# 808sn.net
KiCad netlist of a schematic drawn in EAGLE
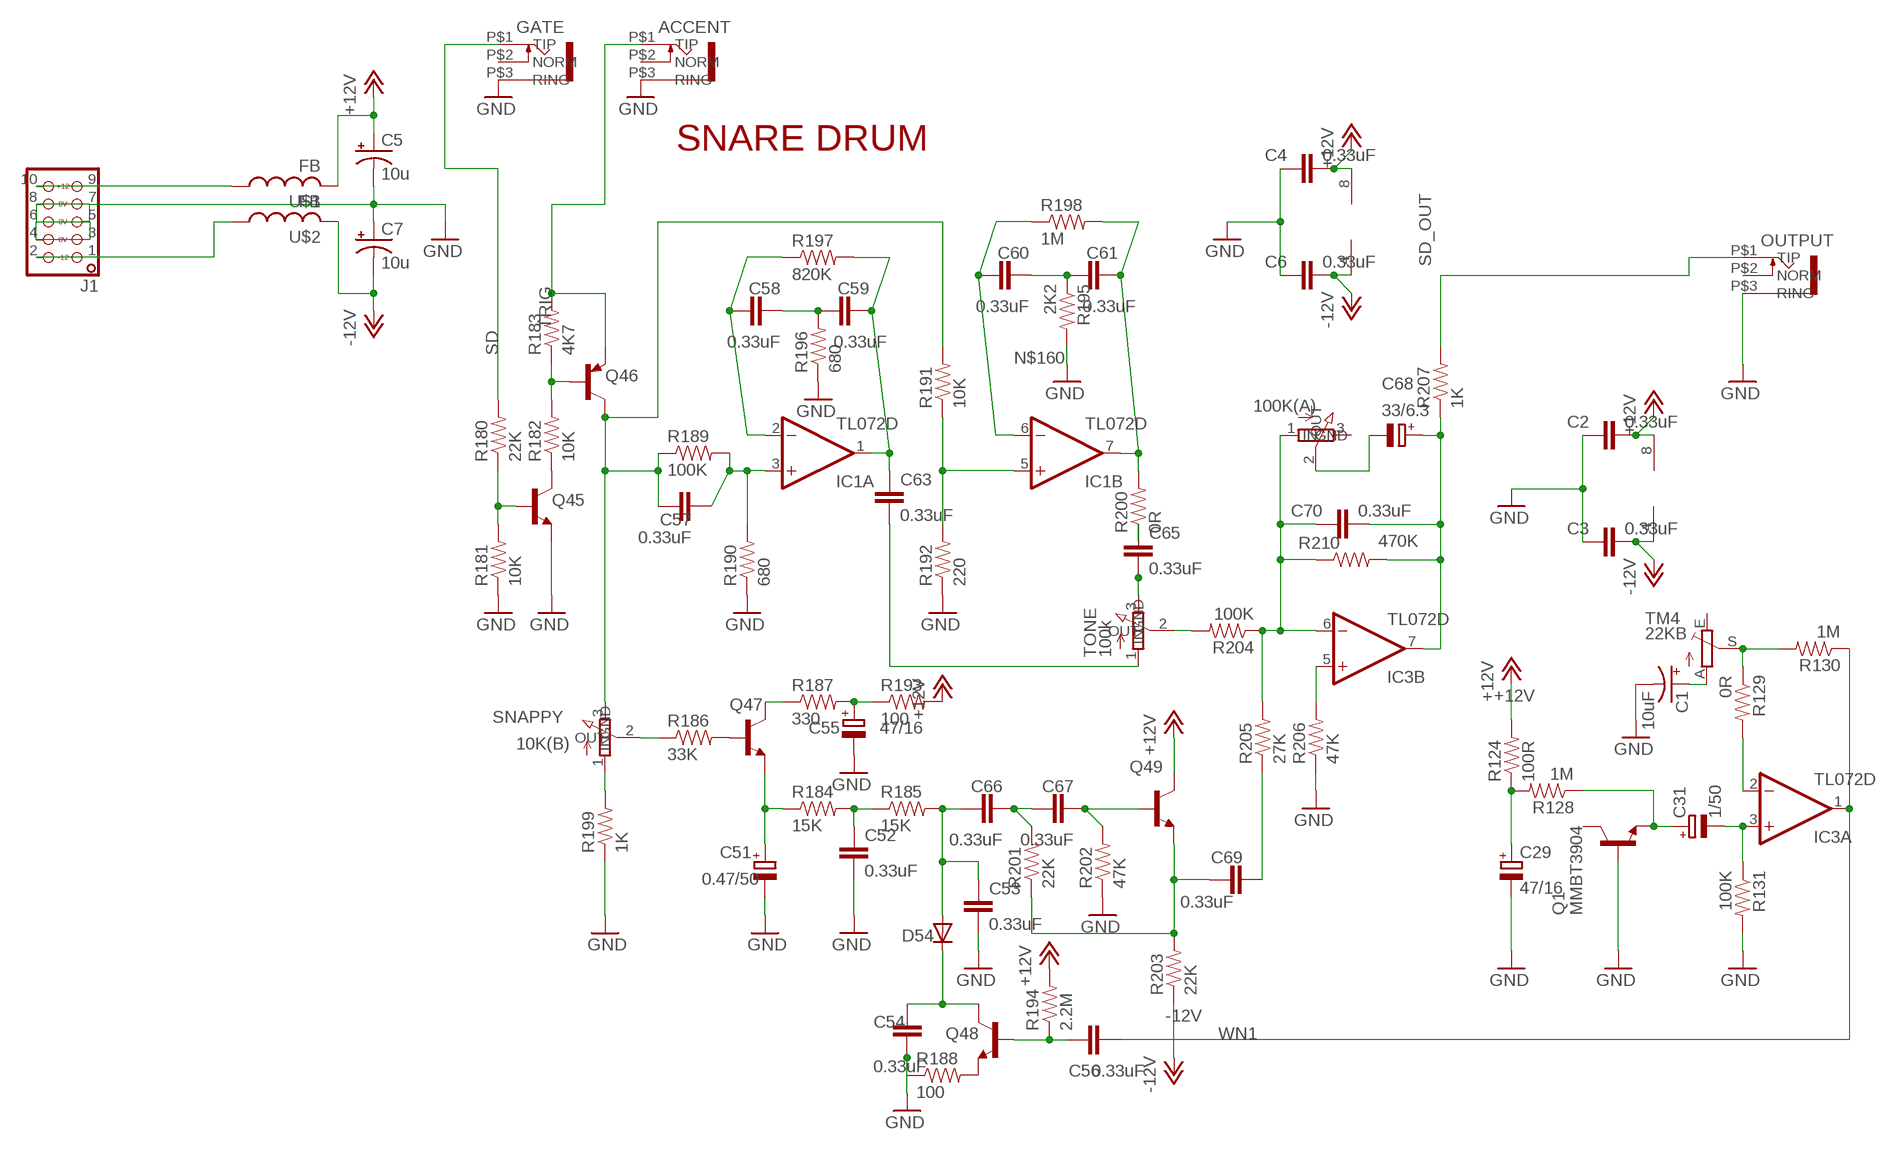
[diagram p0: schematic, sheet 1]

(export (version "E")
  (design (tool "Eeschema 10.0.6"))
  (components
    (comp (ref "ACCENT")
      (value "VERTICALJACKS")
      (footprint "eagle-import:KOBICONN_PJM301DM_JACK")
      (libsource (lib "eagle-import") (part "VERTICALJACKS"))
    )
    (comp (ref "C1")
      (value "10uF")
      (footprint "eagle-import:B45181A")
      (libsource (lib "eagle-import") (part "CPOL-USB45181A"))
    )
    (comp (ref "C2")
      (value "0.33uF")
      (footprint "eagle-import:0805-CAP")
      (libsource (lib "eagle-import") (part "CAPACITOR_0805_HAND"))
    )
    (comp (ref "C3")
      (value "0.33uF")
      (footprint "eagle-import:0805-CAP")
      (libsource (lib "eagle-import") (part "CAPACITOR_0805_HAND"))
    )
    (comp (ref "C4")
      (value "0.33uF")
      (footprint "eagle-import:0805-CAP")
      (libsource (lib "eagle-import") (part "CAPACITOR_0805_HAND"))
    )
    (comp (ref "C5")
      (value "10u")
      (footprint "eagle-import:B45181A")
      (libsource (lib "eagle-import") (part "CPOL-USB45181A"))
    )
    (comp (ref "C6")
      (value "0.33uF")
      (footprint "eagle-import:0805-CAP")
      (libsource (lib "eagle-import") (part "CAPACITOR_0805_HAND"))
    )
    (comp (ref "C7")
      (value "10u")
      (footprint "eagle-import:B45181A")
      (libsource (lib "eagle-import") (part "CPOL-USB45181A"))
    )
    (comp (ref "C29")
      (value "47/16")
      (footprint "eagle-import:E2,5-5")
      (libsource (lib "eagle-import") (part "CPOL-EUE2.5-5"))
    )
    (comp (ref "C31")
      (value "1/50")
      (footprint "eagle-import:E3,5-8")
      (libsource (lib "eagle-import") (part "CPOL-EUE3.5-8"))
    )
    (comp (ref "C51")
      (value "0.47/50")
      (footprint "eagle-import:E3,5-8")
      (libsource (lib "eagle-import") (part "CPOL-EUE3.5-8"))
    )
    (comp (ref "C52")
      (value "0.33uF")
      (footprint "eagle-import:0805-CAP")
      (libsource (lib "eagle-import") (part "CAPACITOR_0805_HAND"))
    )
    (comp (ref "C53")
      (value "0.33uF")
      (footprint "eagle-import:0805-CAP")
      (libsource (lib "eagle-import") (part "CAPACITOR_0805_HAND"))
    )
    (comp (ref "C54")
      (value "0.33uF")
      (footprint "eagle-import:0805-CAP")
      (libsource (lib "eagle-import") (part "CAPACITOR_0805_HAND"))
    )
    (comp (ref "C55")
      (value "47/16")
      (footprint "eagle-import:E2-5")
      (libsource (lib "eagle-import") (part "CPOL-EUE2-5"))
    )
    (comp (ref "C56")
      (value "0.33uF")
      (footprint "eagle-import:0805-CAP")
      (libsource (lib "eagle-import") (part "CAPACITOR_0805_HAND"))
    )
    (comp (ref "C57")
      (value "0.33uF")
      (footprint "eagle-import:0805-CAP")
      (libsource (lib "eagle-import") (part "CAPACITOR_0805_HAND"))
    )
    (comp (ref "C58")
      (value "0.33uF")
      (footprint "eagle-import:0805-CAP")
      (libsource (lib "eagle-import") (part "CAPACITOR_0805_HAND"))
    )
    (comp (ref "C59")
      (value "0.33uF")
      (footprint "eagle-import:0805-CAP")
      (libsource (lib "eagle-import") (part "CAPACITOR_0805_HAND"))
    )
    (comp (ref "C60")
      (value "0.33uF")
      (footprint "eagle-import:0805-CAP")
      (libsource (lib "eagle-import") (part "CAPACITOR_0805_HAND"))
    )
    (comp (ref "C61")
      (value "0.33uF")
      (footprint "eagle-import:0805-CAP")
      (libsource (lib "eagle-import") (part "CAPACITOR_0805_HAND"))
    )
    (comp (ref "C63")
      (value "0.33uF")
      (footprint "eagle-import:0805-CAP")
      (libsource (lib "eagle-import") (part "CAPACITOR_0805_HAND"))
    )
    (comp (ref "C65")
      (value "0.33uF")
      (footprint "eagle-import:0805-CAP")
      (libsource (lib "eagle-import") (part "CAPACITOR_0805_HAND"))
    )
    (comp (ref "C66")
      (value "0.33uF")
      (footprint "eagle-import:0805-CAP")
      (libsource (lib "eagle-import") (part "CAPACITOR_0805_HAND"))
    )
    (comp (ref "C67")
      (value "0.33uF")
      (footprint "eagle-import:0805-CAP")
      (libsource (lib "eagle-import") (part "CAPACITOR_0805_HAND"))
    )
    (comp (ref "C68")
      (value "33/6.3")
      (footprint "eagle-import:E2-5")
      (libsource (lib "eagle-import") (part "CPOL-EUE2-5"))
    )
    (comp (ref "C69")
      (value "0.33uF")
      (footprint "eagle-import:0805-CAP")
      (libsource (lib "eagle-import") (part "CAPACITOR_0805_HAND"))
    )
    (comp (ref "C70")
      (value "0.33uF")
      (footprint "eagle-import:0805-CAP")
      (libsource (lib "eagle-import") (part "CAPACITOR_0805_HAND"))
    )
    (comp (ref "D54")
      (value "1N4148SOD-323")
      (footprint "eagle-import:SOD323W_INFINEON")
      (libsource (lib "eagle-import") (part "1N4148SOD-323"))
    )
    (comp (ref "GATE")
      (value "VERTICALJACKS")
      (footprint "eagle-import:KOBICONN_PJM301DM_JACK")
      (libsource (lib "eagle-import") (part "VERTICALJACKS"))
    )
    (comp (ref "IC1")
      (value "TL072D")
      (footprint "eagle-import:SO08")
      (libsource (lib "eagle-import") (part "TL072D"))
    )
    (comp (ref "IC3")
      (value "TL072D")
      (footprint "eagle-import:SO08")
      (libsource (lib "eagle-import") (part "TL072D"))
    )
    (comp (ref "J1")
      (value "EUROPWR_2X05-OPEN")
      (footprint "eagle-import:2X05_EUROPWR_OPEN")
      (libsource (lib "eagle-import") (part "EUROPWR_2X05-OPEN"))
    )
    (comp (ref "LEVEL")
      (value "100K(A)")
      (footprint "eagle-import:ALPHA_9MM_VERTICAL")
      (libsource (lib "eagle-import") (part "PCB_POTS"))
    )
    (comp (ref "OUTPUT")
      (value "VERTICALJACKS")
      (footprint "eagle-import:KOBICONN_PJM301DM_JACK")
      (libsource (lib "eagle-import") (part "VERTICALJACKS"))
    )
    (comp (ref "Q1")
      (value "MMBT3904")
      (footprint "eagle-import:SOT23-BEC")
      (libsource (lib "eagle-import") (part "-NPN-SOT23-BECMMBT3904LT1"))
    )
    (comp (ref "Q45")
      (value "MMBT3904")
      (footprint "eagle-import:SOT23-BEC")
      (libsource (lib "eagle-import") (part "-NPN-SOT23-BECMMBT3904LT1"))
    )
    (comp (ref "Q46")
      (value "MMBT3906")
      (footprint "eagle-import:SOT23-BEC")
      (libsource (lib "eagle-import") (part "-PNP-SOT23-BECMMBT3906LT1"))
    )
    (comp (ref "Q47")
      (value "MMBT3904")
      (footprint "eagle-import:SOT23-BEC")
      (libsource (lib "eagle-import") (part "-NPN-SOT23-BECMMBT3904LT1"))
    )
    (comp (ref "Q48")
      (value "MMBT3904")
      (footprint "eagle-import:SOT23-BEC")
      (libsource (lib "eagle-import") (part "-NPN-SOT23-BECMMBT3904LT1"))
    )
    (comp (ref "Q49")
      (value "MMBT3904")
      (footprint "eagle-import:SOT23-BEC")
      (libsource (lib "eagle-import") (part "-NPN-SOT23-BECMMBT3904LT1"))
    )
    (comp (ref "R124")
      (value "100R")
      (footprint "eagle-import:0805_RESISTOR")
      (libsource (lib "eagle-import") (part "RESISTOR_0805_HAND"))
    )
    (comp (ref "R128")
      (value "1M")
      (footprint "eagle-import:0805_RESISTOR")
      (libsource (lib "eagle-import") (part "RESISTOR_0805_HAND"))
    )
    (comp (ref "R129")
      (value "0R")
      (footprint "eagle-import:0805_RESISTOR")
      (libsource (lib "eagle-import") (part "RESISTOR_0805_HAND"))
    )
    (comp (ref "R130")
      (value "1M")
      (footprint "eagle-import:0805_RESISTOR")
      (libsource (lib "eagle-import") (part "RESISTOR_0805_HAND"))
    )
    (comp (ref "R131")
      (value "100K")
      (footprint "eagle-import:0805_RESISTOR")
      (libsource (lib "eagle-import") (part "RESISTOR_0805_HAND"))
    )
    (comp (ref "R180")
      (value "22K")
      (footprint "eagle-import:0805_RESISTOR")
      (libsource (lib "eagle-import") (part "RESISTOR_0805_HAND"))
    )
    (comp (ref "R181")
      (value "10K")
      (footprint "eagle-import:0805_RESISTOR")
      (libsource (lib "eagle-import") (part "RESISTOR_0805_HAND"))
    )
    (comp (ref "R182")
      (value "10K")
      (footprint "eagle-import:0805_RESISTOR")
      (libsource (lib "eagle-import") (part "RESISTOR_0805_HAND"))
    )
    (comp (ref "R183")
      (value "4K7")
      (footprint "eagle-import:0805_RESISTOR")
      (libsource (lib "eagle-import") (part "RESISTOR_0805_HAND"))
    )
    (comp (ref "R184")
      (value "15K")
      (footprint "eagle-import:0805_RESISTOR")
      (libsource (lib "eagle-import") (part "RESISTOR_0805_HAND"))
    )
    (comp (ref "R185")
      (value "15K")
      (footprint "eagle-import:0805_RESISTOR")
      (libsource (lib "eagle-import") (part "RESISTOR_0805_HAND"))
    )
    (comp (ref "R186")
      (value "33K")
      (footprint "eagle-import:0805_RESISTOR")
      (libsource (lib "eagle-import") (part "RESISTOR_0805_HAND"))
    )
    (comp (ref "R187")
      (value "330")
      (footprint "eagle-import:0805_RESISTOR")
      (libsource (lib "eagle-import") (part "RESISTOR_0805_HAND"))
    )
    (comp (ref "R188")
      (value "100")
      (footprint "eagle-import:0805_RESISTOR")
      (libsource (lib "eagle-import") (part "RESISTOR_0805_HAND"))
    )
    (comp (ref "R189")
      (value "100K")
      (footprint "eagle-import:0805_RESISTOR")
      (libsource (lib "eagle-import") (part "RESISTOR_0805_HAND"))
    )
    (comp (ref "R190")
      (value "680")
      (footprint "eagle-import:0805_RESISTOR")
      (libsource (lib "eagle-import") (part "RESISTOR_0805_HAND"))
    )
    (comp (ref "R191")
      (value "10K")
      (footprint "eagle-import:0805_RESISTOR")
      (libsource (lib "eagle-import") (part "RESISTOR_0805_HAND"))
    )
    (comp (ref "R192")
      (value "220")
      (footprint "eagle-import:0805_RESISTOR")
      (libsource (lib "eagle-import") (part "RESISTOR_0805_HAND"))
    )
    (comp (ref "R193")
      (value "100")
      (footprint "eagle-import:0805_RESISTOR")
      (libsource (lib "eagle-import") (part "RESISTOR_0805_HAND"))
    )
    (comp (ref "R194")
      (value "2.2M")
      (footprint "eagle-import:0805_RESISTOR")
      (libsource (lib "eagle-import") (part "RESISTOR_0805_HAND"))
    )
    (comp (ref "R195")
      (value "2K2")
      (footprint "eagle-import:0805_RESISTOR")
      (libsource (lib "eagle-import") (part "RESISTOR_0805_HAND"))
    )
    (comp (ref "R196")
      (value "680")
      (footprint "eagle-import:0805_RESISTOR")
      (libsource (lib "eagle-import") (part "RESISTOR_0805_HAND"))
    )
    (comp (ref "R197")
      (value "820K")
      (footprint "eagle-import:0805_RESISTOR")
      (libsource (lib "eagle-import") (part "RESISTOR_0805_HAND"))
    )
    (comp (ref "R198")
      (value "1M")
      (footprint "eagle-import:0805_RESISTOR")
      (libsource (lib "eagle-import") (part "RESISTOR_0805_HAND"))
    )
    (comp (ref "R199")
      (value "1K")
      (footprint "eagle-import:0805_RESISTOR")
      (libsource (lib "eagle-import") (part "RESISTOR_0805_HAND"))
    )
    (comp (ref "R200")
      (value "0R")
      (footprint "eagle-import:0805_RESISTOR")
      (libsource (lib "eagle-import") (part "RESISTOR_0805_HAND"))
    )
    (comp (ref "R201")
      (value "22K")
      (footprint "eagle-import:0805_RESISTOR")
      (libsource (lib "eagle-import") (part "RESISTOR_0805_HAND"))
    )
    (comp (ref "R202")
      (value "47K")
      (footprint "eagle-import:0805_RESISTOR")
      (libsource (lib "eagle-import") (part "RESISTOR_0805_HAND"))
    )
    (comp (ref "R203")
      (value "22K")
      (footprint "eagle-import:0805_RESISTOR")
      (libsource (lib "eagle-import") (part "RESISTOR_0805_HAND"))
    )
    (comp (ref "R204")
      (value "100K")
      (footprint "eagle-import:0805_RESISTOR")
      (libsource (lib "eagle-import") (part "RESISTOR_0805_HAND"))
    )
    (comp (ref "R205")
      (value "27K")
      (footprint "eagle-import:0805_RESISTOR")
      (libsource (lib "eagle-import") (part "RESISTOR_0805_HAND"))
    )
    (comp (ref "R206")
      (value "47K")
      (footprint "eagle-import:0805_RESISTOR")
      (libsource (lib "eagle-import") (part "RESISTOR_0805_HAND"))
    )
    (comp (ref "R207")
      (value "1K")
      (footprint "eagle-import:0805_RESISTOR")
      (libsource (lib "eagle-import") (part "RESISTOR_0805_HAND"))
    )
    (comp (ref "R210")
      (value "470K")
      (footprint "eagle-import:0805_RESISTOR")
      (libsource (lib "eagle-import") (part "RESISTOR_0805_HAND"))
    )
    (comp (ref "SNAPPY")
      (value "10K(B)")
      (footprint "eagle-import:ALPHA_9MM_VERTICAL")
      (libsource (lib "eagle-import") (part "PCB_POTS"))
    )
    (comp (ref "TM4")
      (value "22KB")
      (footprint "eagle-import:B64Y")
      (libsource (lib "eagle-import") (part "TRIM_EU-B64Y"))
    )
    (comp (ref "TONE")
      (value "100k")
      (footprint "eagle-import:ALPHA_9MM_VERTICAL")
      (libsource (lib "eagle-import") (part "PCB_POTS"))
    )
    (comp (ref "U$1") (value "FB") (footprint "eagle-import:FB") (libsource (lib "eagle-import") (part "FB")))
    (comp (ref "U$2") (value "FB") (footprint "eagle-import:FB") (libsource (lib "eagle-import") (part "FB")))
  )
  (nets
    (net (code "1") (name "+12V") (class "Default")
      (node (ref "C2") (pin "2") (pinfunction "2_2") (pintype "passive"))
      (node (ref "C4") (pin "2") (pinfunction "2_2") (pintype "passive"))
      (node (ref "C5") (pin "+") (pinfunction "+_+") (pintype "passive"))
      (node (ref "IC1") (pin "8") (pinfunction "V+_8") (pintype "power_in"))
      (node (ref "IC3") (pin "8") (pinfunction "V+_8") (pintype "power_in"))
      (node (ref "Q49") (pin "C") (pinfunction "C_C") (pintype "passive"))
      (node (ref "R124") (pin "2") (pinfunction "2_2") (pintype "passive"))
      (node (ref "R193") (pin "2") (pinfunction "2_2") (pintype "passive"))
      (node (ref "R194") (pin "2") (pinfunction "2_2") (pintype "passive"))
      (node (ref "U$1") (pin "P$2") (pinfunction "2_P$2") (pintype "passive"))
    )
    (net (code "2") (name "-12V") (class "Default")
      (node (ref "C3") (pin "2") (pinfunction "2_2") (pintype "passive"))
      (node (ref "C6") (pin "2") (pinfunction "2_2") (pintype "passive"))
      (node (ref "C7") (pin "-") (pinfunction "-_-") (pintype "passive"))
      (node (ref "IC1") (pin "4") (pinfunction "V-_4") (pintype "power_in"))
      (node (ref "IC3") (pin "4") (pinfunction "V-_4") (pintype "power_in"))
      (node (ref "R203") (pin "1") (pinfunction "1_1") (pintype "passive"))
      (node (ref "U$2") (pin "P$2") (pinfunction "2_P$2") (pintype "passive"))
    )
    (net (code "3") (name "/N$160") (class "Default")
      (node (ref "C60") (pin "1") (pinfunction "1_1") (pintype "passive"))
      (node (ref "IC1") (pin "6") (pinfunction "-IN_6") (pintype "input"))
      (node (ref "R198") (pin "1") (pinfunction "1_1") (pintype "passive"))
    )
    (net (code "4") (name "/SD") (class "Default")
      (node (ref "GATE") (pin "P$1") (pinfunction "TIP_P$1") (pintype "passive"))
      (node (ref "R180") (pin "2") (pinfunction "2_2") (pintype "passive"))
    )
    (net (code "5") (name "/SD_OUT") (class "Default")
      (node (ref "OUTPUT") (pin "P$1") (pinfunction "TIP_P$1") (pintype "passive"))
      (node (ref "R207") (pin "2") (pinfunction "2_2") (pintype "passive"))
    )
    (net (code "6") (name "/TRIG") (class "Default")
      (node (ref "ACCENT") (pin "P$1") (pinfunction "TIP_P$1") (pintype "passive"))
      (node (ref "Q46") (pin "E") (pinfunction "E_E") (pintype "passive"))
      (node (ref "R183") (pin "2") (pinfunction "2_2") (pintype "passive"))
    )
    (net (code "7") (name "/WN1") (class "Default")
      (node (ref "C56") (pin "2") (pinfunction "2_2") (pintype "passive"))
      (node (ref "IC3") (pin "1") (pinfunction "OUT_1") (pintype "output"))
      (node (ref "R130") (pin "1") (pinfunction "1_1") (pintype "passive"))
    )
    (net (code "8") (name "GND") (class "Default")
      (node (ref "ACCENT") (pin "P$3") (pinfunction "RING_P$3") (pintype "passive"))
      (node (ref "C1") (pin "-") (pinfunction "-_-") (pintype "passive"))
      (node (ref "C2") (pin "1") (pinfunction "1_1") (pintype "passive"))
      (node (ref "C29") (pin "-") (pinfunction "-_-") (pintype "passive"))
      (node (ref "C3") (pin "1") (pinfunction "1_1") (pintype "passive"))
      (node (ref "C4") (pin "1") (pinfunction "1_1") (pintype "passive"))
      (node (ref "C5") (pin "-") (pinfunction "-_-") (pintype "passive"))
      (node (ref "C51") (pin "-") (pinfunction "-_-") (pintype "passive"))
      (node (ref "C52") (pin "2") (pinfunction "2_2") (pintype "passive"))
      (node (ref "C53") (pin "2") (pinfunction "2_2") (pintype "passive"))
      (node (ref "C54") (pin "2") (pinfunction "2_2") (pintype "passive"))
      (node (ref "C55") (pin "-") (pinfunction "-_-") (pintype "passive"))
      (node (ref "C6") (pin "1") (pinfunction "1_1") (pintype "passive"))
      (node (ref "C7") (pin "+") (pinfunction "+_+") (pintype "passive"))
      (node (ref "GATE") (pin "P$3") (pinfunction "RING_P$3") (pintype "passive"))
      (node (ref "J1") (pin "3") (pinfunction "3_3") (pintype "passive"))
      (node (ref "J1") (pin "4") (pinfunction "4_4") (pintype "passive"))
      (node (ref "J1") (pin "5") (pinfunction "5_5") (pintype "passive"))
      (node (ref "J1") (pin "6") (pinfunction "6_6") (pintype "passive"))
      (node (ref "J1") (pin "7") (pinfunction "7_7") (pintype "passive"))
      (node (ref "J1") (pin "8") (pinfunction "8_8") (pintype "passive"))
      (node (ref "OUTPUT") (pin "P$3") (pinfunction "RING_P$3") (pintype "passive"))
      (node (ref "Q1") (pin "B") (pinfunction "B_B") (pintype "passive"))
      (node (ref "Q45") (pin "E") (pinfunction "E_E") (pintype "passive"))
      (node (ref "R131") (pin "2") (pinfunction "2_2") (pintype "passive"))
      (node (ref "R181") (pin "1") (pinfunction "1_1") (pintype "passive"))
      (node (ref "R188") (pin "1") (pinfunction "1_1") (pintype "passive"))
      (node (ref "R190") (pin "1") (pinfunction "1_1") (pintype "passive"))
      (node (ref "R192") (pin "1") (pinfunction "1_1") (pintype "passive"))
      (node (ref "R195") (pin "2") (pinfunction "2_2") (pintype "passive"))
      (node (ref "R196") (pin "1") (pinfunction "1_1") (pintype "passive"))
      (node (ref "R199") (pin "1") (pinfunction "1_1") (pintype "passive"))
      (node (ref "R202") (pin "1") (pinfunction "1_1") (pintype "passive"))
      (node (ref "R206") (pin "1") (pinfunction "1_1") (pintype "passive"))
    )
    (net (code "9") (name "Net-(C1-Pad+)") (class "Default")
      (node (ref "C1") (pin "+") (pinfunction "+_+") (pintype "passive"))
      (node (ref "TM4") (pin "A") (pinfunction "A_A") (pintype "passive"))
    )
    (net (code "10") (name "Net-(C29-Pad+)") (class "Default")
      (node (ref "C29") (pin "+") (pinfunction "+_+") (pintype "passive"))
      (node (ref "R124") (pin "1") (pinfunction "1_1") (pintype "passive"))
      (node (ref "R128") (pin "2") (pinfunction "2_2") (pintype "passive"))
    )
    (net (code "11") (name "Net-(C31-Pad+)") (class "Default")
      (node (ref "C31") (pin "+") (pinfunction "+_+") (pintype "passive"))
      (node (ref "Q1") (pin "E") (pinfunction "E_E") (pintype "passive"))
      (node (ref "R128") (pin "1") (pinfunction "1_1") (pintype "passive"))
    )
    (net (code "12") (name "Net-(C51-Pad+)") (class "Default")
      (node (ref "C51") (pin "+") (pinfunction "+_+") (pintype "passive"))
      (node (ref "Q47") (pin "E") (pinfunction "E_E") (pintype "passive"))
      (node (ref "R184") (pin "1") (pinfunction "1_1") (pintype "passive"))
    )
    (net (code "13") (name "Net-(C52-Pad1)") (class "Default")
      (node (ref "C52") (pin "1") (pinfunction "1_1") (pintype "passive"))
      (node (ref "R184") (pin "2") (pinfunction "2_2") (pintype "passive"))
      (node (ref "R185") (pin "1") (pinfunction "1_1") (pintype "passive"))
    )
    (net (code "14") (name "Net-(C53-Pad1)") (class "Default")
      (node (ref "C53") (pin "1") (pinfunction "1_1") (pintype "passive"))
      (node (ref "C66") (pin "1") (pinfunction "1_1") (pintype "passive"))
      (node (ref "D54") (pin "A") (pinfunction "A_A") (pintype "passive"))
      (node (ref "R185") (pin "2") (pinfunction "2_2") (pintype "passive"))
    )
    (net (code "15") (name "Net-(C54-Pad1)") (class "Default")
      (node (ref "C54") (pin "1") (pinfunction "1_1") (pintype "passive"))
      (node (ref "D54") (pin "C") (pinfunction "C_C") (pintype "passive"))
      (node (ref "Q48") (pin "C") (pinfunction "C_C") (pintype "passive"))
    )
    (net (code "16") (name "Net-(C55-Pad+)") (class "Default")
      (node (ref "C55") (pin "+") (pinfunction "+_+") (pintype "passive"))
      (node (ref "R187") (pin "2") (pinfunction "2_2") (pintype "passive"))
      (node (ref "R193") (pin "1") (pinfunction "1_1") (pintype "passive"))
    )
    (net (code "17") (name "Net-(C56-Pad1)") (class "Default")
      (node (ref "C56") (pin "1") (pinfunction "1_1") (pintype "passive"))
      (node (ref "Q48") (pin "B") (pinfunction "B_B") (pintype "passive"))
      (node (ref "R194") (pin "1") (pinfunction "1_1") (pintype "passive"))
    )
    (net (code "18") (name "Net-(C58-Pad2)") (class "Default")
      (node (ref "C58") (pin "2") (pinfunction "2_2") (pintype "passive"))
      (node (ref "C59") (pin "1") (pinfunction "1_1") (pintype "passive"))
      (node (ref "R196") (pin "2") (pinfunction "2_2") (pintype "passive"))
    )
    (net (code "19") (name "Net-(C60-Pad2)") (class "Default")
      (node (ref "C60") (pin "2") (pinfunction "2_2") (pintype "passive"))
      (node (ref "C61") (pin "1") (pinfunction "1_1") (pintype "passive"))
      (node (ref "R195") (pin "1") (pinfunction "1_1") (pintype "passive"))
    )
    (net (code "20") (name "Net-(C65-Pad1)") (class "Default")
      (node (ref "C65") (pin "1") (pinfunction "1_1") (pintype "passive"))
      (node (ref "R200") (pin "1") (pinfunction "1_1") (pintype "passive"))
    )
    (net (code "21") (name "Net-(C66-Pad2)") (class "Default")
      (node (ref "C66") (pin "2") (pinfunction "2_2") (pintype "passive"))
      (node (ref "C67") (pin "1") (pinfunction "1_1") (pintype "passive"))
      (node (ref "R201") (pin "2") (pinfunction "2_2") (pintype "passive"))
    )
    (net (code "22") (name "Net-(C67-Pad2)") (class "Default")
      (node (ref "C67") (pin "2") (pinfunction "2_2") (pintype "passive"))
      (node (ref "Q49") (pin "B") (pinfunction "B_B") (pintype "passive"))
      (node (ref "R202") (pin "2") (pinfunction "2_2") (pintype "passive"))
    )
    (net (code "23") (name "Net-(C69-Pad1)") (class "Default")
      (node (ref "C69") (pin "1") (pinfunction "1_1") (pintype "passive"))
      (node (ref "Q49") (pin "E") (pinfunction "E_E") (pintype "passive"))
      (node (ref "R201") (pin "1") (pinfunction "1_1") (pintype "passive"))
      (node (ref "R203") (pin "2") (pinfunction "2_2") (pintype "passive"))
    )
    (net (code "24") (name "Net-(C69-Pad2)") (class "Default")
      (node (ref "C69") (pin "2") (pinfunction "2_2") (pintype "passive"))
      (node (ref "R205") (pin "1") (pinfunction "1_1") (pintype "passive"))
    )
    (net (code "25") (name "Net-(IC1A-+IN)") (class "Default")
      (node (ref "C57") (pin "2") (pinfunction "2_2") (pintype "passive"))
      (node (ref "IC1") (pin "3") (pinfunction "+IN_3") (pintype "input"))
      (node (ref "R189") (pin "2") (pinfunction "2_2") (pintype "passive"))
      (node (ref "R190") (pin "2") (pinfunction "2_2") (pintype "passive"))
    )
    (net (code "26") (name "Net-(IC1A--IN)") (class "Default")
      (node (ref "C58") (pin "1") (pinfunction "1_1") (pintype "passive"))
      (node (ref "IC1") (pin "2") (pinfunction "-IN_2") (pintype "input"))
      (node (ref "R197") (pin "1") (pinfunction "1_1") (pintype "passive"))
    )
    (net (code "27") (name "Net-(IC1A-OUT)") (class "Default")
      (node (ref "C59") (pin "2") (pinfunction "2_2") (pintype "passive"))
      (node (ref "C63") (pin "1") (pinfunction "1_1") (pintype "passive"))
      (node (ref "IC1") (pin "1") (pinfunction "OUT_1") (pintype "output"))
      (node (ref "R197") (pin "2") (pinfunction "2_2") (pintype "passive"))
    )
    (net (code "28") (name "Net-(IC1B-+IN)") (class "Default")
      (node (ref "IC1") (pin "5") (pinfunction "+IN_5") (pintype "input"))
      (node (ref "R191") (pin "1") (pinfunction "1_1") (pintype "passive"))
      (node (ref "R192") (pin "2") (pinfunction "2_2") (pintype "passive"))
    )
    (net (code "29") (name "Net-(IC1B-OUT)") (class "Default")
      (node (ref "C61") (pin "2") (pinfunction "2_2") (pintype "passive"))
      (node (ref "IC1") (pin "7") (pinfunction "OUT_7") (pintype "output"))
      (node (ref "R198") (pin "2") (pinfunction "2_2") (pintype "passive"))
      (node (ref "R200") (pin "2") (pinfunction "2_2") (pintype "passive"))
    )
    (net (code "30") (name "Net-(IC3A-+IN)") (class "Default")
      (node (ref "C31") (pin "-") (pinfunction "-_-") (pintype "passive"))
      (node (ref "IC3") (pin "3") (pinfunction "+IN_3") (pintype "input"))
      (node (ref "R131") (pin "1") (pinfunction "1_1") (pintype "passive"))
    )
    (net (code "31") (name "Net-(IC3A--IN)") (class "Default")
      (node (ref "IC3") (pin "2") (pinfunction "-IN_2") (pintype "input"))
      (node (ref "R129") (pin "2") (pinfunction "2_2") (pintype "passive"))
    )
    (net (code "32") (name "Net-(IC3B-+IN)") (class "Default")
      (node (ref "IC3") (pin "5") (pinfunction "+IN_5") (pintype "input"))
      (node (ref "R206") (pin "2") (pinfunction "2_2") (pintype "passive"))
    )
    (net (code "33") (name "Net-(IC3B--IN)") (class "Default")
      (node (ref "C70") (pin "1") (pinfunction "1_1") (pintype "passive"))
      (node (ref "IC3") (pin "6") (pinfunction "-IN_6") (pintype "input"))
      (node (ref "LEVEL") (pin "1") (pinfunction "GND_1") (pintype "passive"))
      (node (ref "R204") (pin "1") (pinfunction "1_1") (pintype "passive"))
      (node (ref "R205") (pin "2") (pinfunction "2_2") (pintype "passive"))
      (node (ref "R210") (pin "1") (pinfunction "1_1") (pintype "passive"))
    )
    (net (code "34") (name "Net-(IC3B-OUT)") (class "Default")
      (node (ref "C68") (pin "+") (pinfunction "+_+") (pintype "passive"))
      (node (ref "C70") (pin "2") (pinfunction "2_2") (pintype "passive"))
      (node (ref "IC3") (pin "7") (pinfunction "OUT_7") (pintype "output"))
      (node (ref "R207") (pin "1") (pinfunction "1_1") (pintype "passive"))
      (node (ref "R210") (pin "2") (pinfunction "2_2") (pintype "passive"))
    )
    (net (code "35") (name "Net-(LEVEL-OUT)") (class "Default")
      (node (ref "C68") (pin "-") (pinfunction "-_-") (pintype "passive"))
      (node (ref "LEVEL") (pin "2") (pinfunction "OUT_2") (pintype "passive"))
    )
    (net (code "36") (name "Net-(Q45-PadB)") (class "Default")
      (node (ref "Q45") (pin "B") (pinfunction "B_B") (pintype "passive"))
      (node (ref "R180") (pin "1") (pinfunction "1_1") (pintype "passive"))
      (node (ref "R181") (pin "2") (pinfunction "2_2") (pintype "passive"))
    )
    (net (code "37") (name "Net-(Q45-PadC)") (class "Default")
      (node (ref "Q45") (pin "C") (pinfunction "C_C") (pintype "passive"))
      (node (ref "R182") (pin "1") (pinfunction "1_1") (pintype "passive"))
    )
    (net (code "38") (name "Net-(Q46-PadB)") (class "Default")
      (node (ref "Q46") (pin "B") (pinfunction "B_B") (pintype "passive"))
      (node (ref "R182") (pin "2") (pinfunction "2_2") (pintype "passive"))
      (node (ref "R183") (pin "1") (pinfunction "1_1") (pintype "passive"))
    )
    (net (code "39") (name "Net-(Q47-PadB)") (class "Default")
      (node (ref "Q47") (pin "B") (pinfunction "B_B") (pintype "passive"))
      (node (ref "R186") (pin "2") (pinfunction "2_2") (pintype "passive"))
    )
    (net (code "40") (name "Net-(Q47-PadC)") (class "Default")
      (node (ref "Q47") (pin "C") (pinfunction "C_C") (pintype "passive"))
      (node (ref "R187") (pin "1") (pinfunction "1_1") (pintype "passive"))
    )
    (net (code "41") (name "Net-(Q48-PadE)") (class "Default")
      (node (ref "Q48") (pin "E") (pinfunction "E_E") (pintype "passive"))
      (node (ref "R188") (pin "2") (pinfunction "2_2") (pintype "passive"))
    )
    (net (code "42") (name "Net-(R129-Pad1)") (class "Default")
      (node (ref "R129") (pin "1") (pinfunction "1_1") (pintype "passive"))
      (node (ref "R130") (pin "2") (pinfunction "2_2") (pintype "passive"))
      (node (ref "TM4") (pin "S") (pinfunction "S_S") (pintype "passive"))
    )
    (net (code "43") (name "Net-(SNAPPY-GND)") (class "Default")
      (node (ref "R199") (pin "2") (pinfunction "2_2") (pintype "passive"))
      (node (ref "SNAPPY") (pin "1") (pinfunction "GND_1") (pintype "passive"))
    )
    (net (code "44") (name "Net-(SNAPPY-IN)") (class "Default")
      (node (ref "C57") (pin "1") (pinfunction "1_1") (pintype "passive"))
      (node (ref "Q46") (pin "C") (pinfunction "C_C") (pintype "passive"))
      (node (ref "R189") (pin "1") (pinfunction "1_1") (pintype "passive"))
      (node (ref "R191") (pin "2") (pinfunction "2_2") (pintype "passive"))
      (node (ref "SNAPPY") (pin "3") (pinfunction "IN_3") (pintype "passive"))
    )
    (net (code "45") (name "Net-(SNAPPY-OUT)") (class "Default")
      (node (ref "R186") (pin "1") (pinfunction "1_1") (pintype "passive"))
      (node (ref "SNAPPY") (pin "2") (pinfunction "OUT_2") (pintype "passive"))
    )
    (net (code "46") (name "Net-(TONE-GND)") (class "Default")
      (node (ref "C63") (pin "2") (pinfunction "2_2") (pintype "passive"))
      (node (ref "TONE") (pin "1") (pinfunction "GND_1") (pintype "passive"))
    )
    (net (code "47") (name "Net-(TONE-IN)") (class "Default")
      (node (ref "C65") (pin "2") (pinfunction "2_2") (pintype "passive"))
      (node (ref "TONE") (pin "3") (pinfunction "IN_3") (pintype "passive"))
    )
    (net (code "48") (name "Net-(TONE-OUT)") (class "Default")
      (node (ref "R204") (pin "2") (pinfunction "2_2") (pintype "passive"))
      (node (ref "TONE") (pin "2") (pinfunction "OUT_2") (pintype "passive"))
    )
    (net (code "49") (name "Net-(U$1-1)") (class "Default")
      (node (ref "J1") (pin "10") (pinfunction "10_10") (pintype "passive"))
      (node (ref "J1") (pin "9") (pinfunction "9_9") (pintype "passive"))
      (node (ref "U$1") (pin "P$1") (pinfunction "1_P$1") (pintype "passive"))
    )
    (net (code "50") (name "Net-(U$2-1)") (class "Default")
      (node (ref "J1") (pin "1") (pinfunction "1_1") (pintype "passive"))
      (node (ref "J1") (pin "2") (pinfunction "2_2") (pintype "passive"))
      (node (ref "U$2") (pin "P$1") (pinfunction "1_P$1") (pintype "passive"))
    )
    (net (code "51") (name "unconnected-(ACCENT-NORM-PadP$2)") (class "Default")
      (node (ref "ACCENT") (pin "P$2") (pinfunction "NORM_P$2") (pintype "passive"))
    )
    (net (code "52") (name "unconnected-(GATE-NORM-PadP$2)") (class "Default")
      (node (ref "GATE") (pin "P$2") (pinfunction "NORM_P$2") (pintype "passive"))
    )
    (net (code "53") (name "unconnected-(LEVEL-IN-Pad3)") (class "Default")
      (node (ref "LEVEL") (pin "3") (pinfunction "IN_3") (pintype "passive"))
    )
    (net (code "54") (name "unconnected-(OUTPUT-NORM-PadP$2)") (class "Default")
      (node (ref "OUTPUT") (pin "P$2") (pinfunction "NORM_P$2") (pintype "passive"))
    )
    (net (code "55") (name "unconnected-(Q1-PadC)") (class "Default")
      (node (ref "Q1") (pin "C") (pinfunction "C_C") (pintype "passive"))
    )
    (net (code "56") (name "unconnected-(TM4-PadE)") (class "Default")
      (node (ref "TM4") (pin "E") (pinfunction "E_E") (pintype "passive"))
    )
  )
)
